# Optical_RX_TX_15-18.net
KiCad netlist of a schematic drawn in Altium Designer
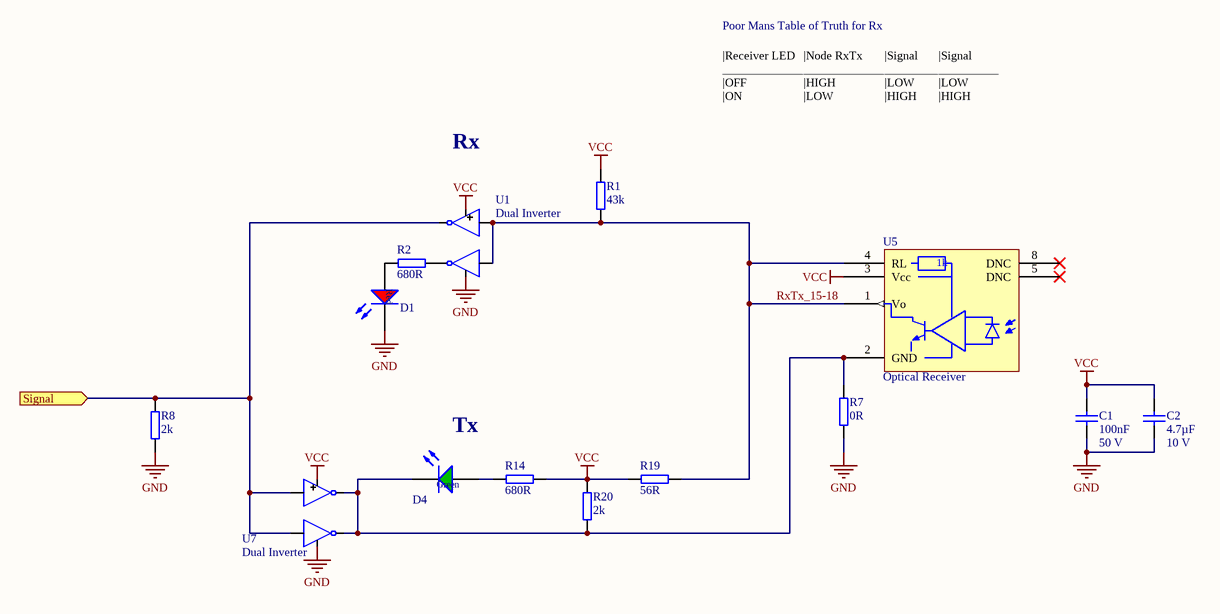
[diagram p0: Optical_RX_TX_15-18.SchDoc]

(export (version "E")
  (design (tool "Eeschema 10.0.6"))
  (components
    (comp (ref "C1")
      (value "100nF")
      (footprint "C_0603(1608)100_L")
      (description "CAP 0603 (1608 Metric) SMD")
      (fields
        (field (name "TOLERANCE") "±5%")
        (field (name "LCSC PART #") "C14663")
        (field (name "RATED VOLTAGE") "50 V")
        (field (name "CREATED") "2018_09_06_AGeiger")
      )
      (libsource (lib "UZOhm_Optical") (part "C_0603"))
    )
    (comp (ref "C2")
      (value "4.7µF")
      (footprint "CAP_2012X06N")
      (description "CAP 0805 (2012 Metric) SMD")
      (fields
        (field (name "TOLERANCE") "±10%")
        (field (name "MF") "Taiyo Yuden")
        (field (name "VOLTAGE") "10 V")
        (field (name "CREATED") "2018_09_06_AGeiger")
      )
      (libsource (lib "UZOhm_Optical") (part "C_0805"))
    )
    (comp (ref "D1")
      (value "150060RS75000")
      (footprint "WL-SMCW_0603")
      (description "WL-SMCW SMD Mono-color Chip LED Waterclear, size 0603, Red, 2 V, 140°")
      (fields
        (field (name "MF") "Wuerth Elektronik")
        (field (name "LCSC PART #") "C2286")
        (field (name "CREATED") "2018_09_06_AGeiger")
      )
      (libsource (lib "UZOhm_Optical") (part "LED_Red_0603"))
    )
    (comp (ref "D4")
      (value "150060GS75000")
      (footprint "WL-SMCW_0603")
      (description "WL-SMCW SMD Mono-color Chip LED Waterclear, size 0603, Green, 3.2 V, 140°")
      (fields
        (field (name "MF") "Wuerth Elektronik")
        (field (name "LCSC PART #") "C72043")
        (field (name "CREATED") "2018_09_06_AGeiger")
      )
      (libsource (lib "UZOhm_Optical") (part "LED_Green_0603"))
    )
    (comp (ref "R1")
      (value "43k")
      (footprint "R_0603_N")
      (description "SMD Resistor 0603")
      (fields
        (field (name "TOLERANCE") "1%")
        (field (name "VOLTAGE") "50V")
        (field (name "CREATED") "2018_09_06_AGeiger")
      )
      (libsource (lib "UZOhm_Optical") (part "R_0603_JLC"))
    )
    (comp (ref "R2")
      (value "680R")
      (footprint "R_0603_N")
      (description "SMD Resistor 0603")
      (fields
        (field (name "TOLERANCE") "1%")
        (field (name "VOLTAGE") "75V")
        (field (name "CREATED") "2018_09_06_AGeiger")
      )
      (libsource (lib "UZOhm_Optical") (part "R_0603"))
    )
    (comp (ref "R7")
      (value "0R")
      (footprint "R_0603_N")
      (description "SMD Resistor 0603")
      (fields
        (field (name "TOLERANCE") "1%")
        (field (name "VOLTAGE") "75V")
        (field (name "CREATED") "2018_09_06_AGeiger")
      )
      (libsource (lib "UZOhm_Optical") (part "R_0603"))
    )
    (comp (ref "R8")
      (value "2k")
      (footprint "R_0603_N")
      (description "SMD Resistor 0603")
      (fields
        (field (name "TOLERANCE") "1%")
        (field (name "VOLTAGE") "75 V")
        (field (name "CREATED") "2018_09_06_AGeiger")
      )
      (libsource (lib "UZOhm_Optical") (part "R_0603"))
    )
    (comp (ref "R14")
      (value "680R")
      (footprint "R_0603_N")
      (description "SMD Resistor 0603")
      (fields
        (field (name "TOLERANCE") "1%")
        (field (name "VOLTAGE") "75V")
        (field (name "CREATED") "2018_09_06_AGeiger")
      )
      (libsource (lib "UZOhm_Optical") (part "R_0603"))
    )
    (comp (ref "R19")
      (value "56R")
      (footprint "RES_2012X06N")
      (description "SMD Resistor 0805")
      (fields (field (name "MF") "Bourns") (field (name "MPN") "CR0805-FX-1200ELF"))
      (libsource (lib "UZOhm_Optical") (part "R_0805"))
    )
    (comp (ref "R20")
      (value "2k")
      (footprint "R_0603_N")
      (description "SMD Resistor 0603")
      (fields
        (field (name "TOLERANCE") "1%")
        (field (name "VOLTAGE") "75 V")
        (field (name "CREATED") "2018_09_06_AGeiger")
      )
      (libsource (lib "UZOhm_Optical") (part "R_0603"))
    )
    (comp (ref "U1")
      (value "Dual Inverter")
      (footprint "SN74LVC2GU04DCKR")
      (description "This dual inverter is designed for 1.65-V to 5.5-V VCC\r\noperation.")
      (fields (field (name "LCSC PART #") "C116660"))
      (libsource (lib "UZOhm_Optical") (part "SN74LVC2GU04DCKR"))
    )
    (comp (ref "U5")
      (value "Optical Receiver")
      (footprint "HFBRx5XX")
      (description "Fibre Optic Receivers, LINK HORIZ 5MBd RC VR RoHS")
      (fields
        (field (name "MF") "Boadcom/Avago")
        (field (name "MPN") "HFBR-2521Z")
        (field (name "CREATED") "2019_04_09_Kreppel")
      )
      (libsource (lib "UZOhm_Optical") (part "HFBR-2528Z"))
    )
    (comp (ref "U7")
      (value "Dual Inverter")
      (footprint "SN74LVC2GU04DCKR")
      (description "This dual inverter is designed for 1.65-V to 5.5-V VCC\r\noperation.")
      (fields (field (name "LCSC PART #") "C116660"))
      (libsource (lib "UZOhm_Optical") (part "SN74LVC2GU04DCKR"))
    )
  )
  (nets
    (net (code "1") (name "/RxTx_15-18") (class "Default")
      (node (ref "R1") (pin "2") (pinfunction "2_2") (pintype "passive"))
      (node (ref "R19") (pin "2") (pintype "passive"))
      (node (ref "U1") (pin "1") (pinfunction "IN1_1") (pintype "passive"))
      (node (ref "U1") (pin "3") (pinfunction "IN2_3") (pintype "passive"))
      (node (ref "U5") (pin "1") (pinfunction "Vo_1") (pintype "output"))
      (node (ref "U5") (pin "4") (pinfunction "RL_4") (pintype "passive"))
    )
    (net (code "2") (name "/Signal") (class "Default")
      (node (ref "R8") (pin "2") (pinfunction "2_2") (pintype "passive"))
      (node (ref "U1") (pin "6") (pinfunction "OUT2_6") (pintype "passive"))
      (node (ref "U7") (pin "1") (pinfunction "IN1_1") (pintype "passive"))
      (node (ref "U7") (pin "3") (pinfunction "IN2_3") (pintype "passive"))
    )
    (net (code "3") (name "GND") (class "Default")
      (node (ref "C1") (pin "2") (pinfunction "2_2") (pintype "passive"))
      (node (ref "C2") (pin "2") (pinfunction "2_2") (pintype "passive"))
      (node (ref "D1") (pin "1") (pinfunction "K_1") (pintype "passive"))
      (node (ref "R7") (pin "2") (pinfunction "2_2") (pintype "passive"))
      (node (ref "R8") (pin "1") (pinfunction "1_1") (pintype "passive"))
      (node (ref "U1") (pin "2") (pinfunction "GND_2") (pintype "passive"))
      (node (ref "U7") (pin "2") (pinfunction "GND_2") (pintype "passive"))
    )
    (net (code "4") (name "Net-(D1-A)") (class "Default")
      (node (ref "D1") (pin "2") (pinfunction "A_2") (pintype "passive"))
      (node (ref "R2") (pin "2") (pinfunction "2_2") (pintype "passive"))
    )
    (net (code "5") (name "Net-(D4-A)") (class "Default")
      (node (ref "D4") (pin "2") (pinfunction "A_2") (pintype "passive"))
      (node (ref "R14") (pin "2") (pinfunction "2_2") (pintype "passive"))
    )
    (net (code "6") (name "Net-(D4-K)") (class "Default")
      (node (ref "D4") (pin "1") (pinfunction "K_1") (pintype "passive"))
      (node (ref "R20") (pin "1") (pinfunction "1_1") (pintype "passive"))
      (node (ref "R7") (pin "1") (pinfunction "1_1") (pintype "passive"))
      (node (ref "U5") (pin "2") (pinfunction "GND_2") (pintype "power_in"))
      (node (ref "U7") (pin "4") (pinfunction "OUT2_4") (pintype "passive"))
      (node (ref "U7") (pin "6") (pinfunction "OUT2_6") (pintype "passive"))
    )
    (net (code "7") (name "Net-(R2-Pad1)") (class "Default")
      (node (ref "R2") (pin "1") (pinfunction "1_1") (pintype "passive"))
      (node (ref "U1") (pin "4") (pinfunction "OUT2_4") (pintype "passive"))
    )
    (net (code "8") (name "VCC") (class "Default")
      (node (ref "C1") (pin "1") (pinfunction "1_1") (pintype "passive"))
      (node (ref "C2") (pin "1") (pinfunction "1_1") (pintype "passive"))
      (node (ref "R1") (pin "1") (pinfunction "1_1") (pintype "passive"))
      (node (ref "R14") (pin "1") (pinfunction "1_1") (pintype "passive"))
      (node (ref "R19") (pin "1") (pintype "passive"))
      (node (ref "R20") (pin "2") (pinfunction "2_2") (pintype "passive"))
      (node (ref "U1") (pin "5") (pinfunction "VCC_5") (pintype "passive"))
      (node (ref "U5") (pin "3") (pinfunction "Vcc_3") (pintype "power_in"))
      (node (ref "U7") (pin "5") (pinfunction "VCC_5") (pintype "passive"))
    )
    (net (code "9") (name "unconnected-(U5-DNC-Pad5)") (class "Default")
      (node (ref "U5") (pin "5") (pinfunction "DNC_5") (pintype "passive+no_connect"))
    )
    (net (code "10") (name "unconnected-(U5-DNC-Pad8)") (class "Default")
      (node (ref "U5") (pin "8") (pinfunction "DNC_8") (pintype "passive+no_connect"))
    )
  )
)
